# rc2014_I2c_ctrl_clock.net
KiCad netlist of a schematic drawn in EAGLE
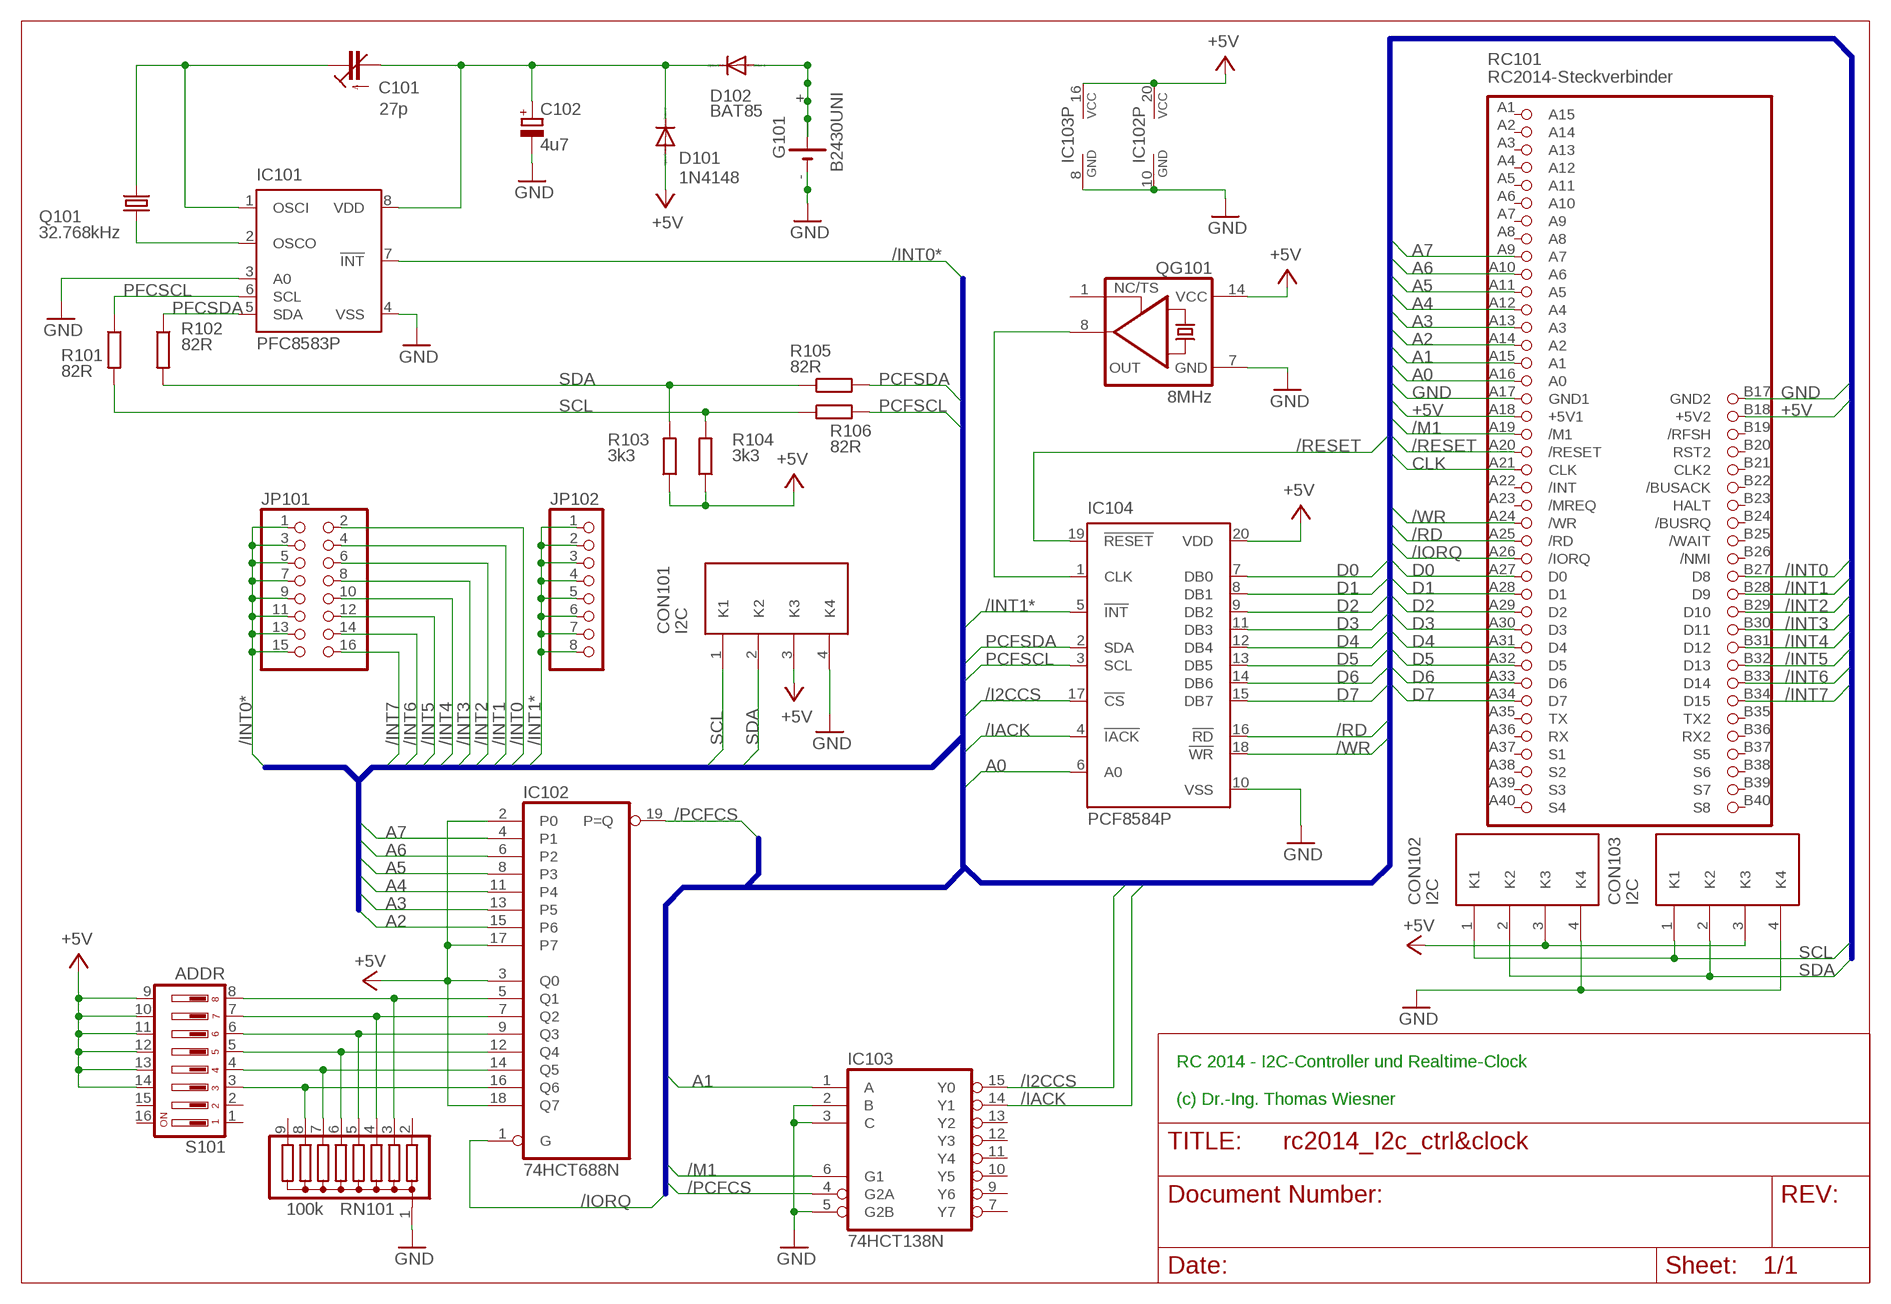
[diagram p0: schematic, sheet 1]

(export (version "E")
  (design (tool "Eeschema 10.0.6"))
  (components
    (comp (ref "C101")
      (value "27p")
      (footprint "eagle-import:CTRIM3050.504")
      (libsource (lib "eagle-import") (part "C-TRIMM3050.504"))
    )
    (comp (ref "C102")
      (value "4u7")
      (footprint "eagle-import:E2,5-6")
      (libsource (lib "eagle-import") (part "CPOL-EUE2.5-6"))
    )
    (comp (ref "CON101")
      (value "I2C")
      (footprint "eagle-import:JST-04-ST90")
      (libsource (lib "eagle-import") (part "SEEED-GROVE"))
    )
    (comp (ref "CON102")
      (value "I2C")
      (footprint "eagle-import:JST-04-ST90")
      (libsource (lib "eagle-import") (part "SEEED-GROVE"))
    )
    (comp (ref "CON103")
      (value "I2C")
      (footprint "eagle-import:JST-04-ST90")
      (libsource (lib "eagle-import") (part "SEEED-GROVE"))
    )
    (comp (ref "D101")
      (value "1N4148")
      (footprint "eagle-import:DO35-7")
      (libsource (lib "eagle-import") (part "1N4148DO35-7"))
    )
    (comp (ref "D102")
      (value "BAT85")
      (footprint "eagle-import:DO34-7")
      (libsource (lib "eagle-import") (part "BAT81"))
    )
    (comp (ref "G101")
      (value "B2430UNI")
      (footprint "eagle-import:B2430UNI")
      (libsource (lib "eagle-import") (part "B2430UNI"))
    )
    (comp (ref "IC101")
      (value "PFC8583P")
      (footprint "eagle-import:DIL08")
      (libsource (lib "eagle-import") (part "PFC8583P"))
    )
    (comp (ref "IC102")
      (value "74HCT688N")
      (footprint "eagle-import:DIL20")
      (libsource (lib "eagle-import") (part "74688NHCT"))
    )
    (comp (ref "IC103")
      (value "74HCT138N")
      (footprint "eagle-import:DIL16")
      (libsource (lib "eagle-import") (part "74138NACT"))
    )
    (comp (ref "IC104")
      (value "PCF8584P")
      (footprint "eagle-import:DIL20")
      (fields (field (name "MF") "FARNELL") (field (name "MPN") "PCF8584P,112"))
      (libsource (lib "eagle-import") (part "PCF8584P"))
    )
    (comp (ref "JP101")
      (value "PINHD-2X8")
      (footprint "eagle-import:2X08")
      (libsource (lib "eagle-import") (part "PINHD-2X8"))
    )
    (comp (ref "JP102")
      (value "PINHD-1X8")
      (footprint "eagle-import:1X08")
      (libsource (lib "eagle-import") (part "PINHD-1X8"))
    )
    (comp (ref "Q101")
      (value "32.768kHz")
      (footprint "eagle-import:TC26H")
      (libsource (lib "eagle-import") (part "CRYSTALTC26H"))
    )
    (comp (ref "QG101")
      (value "8MHz")
      (footprint "eagle-import:DIL14S")
      (libsource (lib "eagle-import") (part "XO-14"))
    )
    (comp (ref "R101")
      (value "82R")
      (footprint "eagle-import:0207_10")
      (libsource (lib "eagle-import") (part "R-EU_0207/10"))
    )
    (comp (ref "R102")
      (value "82R")
      (footprint "eagle-import:0207_10")
      (libsource (lib "eagle-import") (part "R-EU_0207/10"))
    )
    (comp (ref "R103")
      (value "3k3")
      (footprint "eagle-import:0207_10")
      (libsource (lib "eagle-import") (part "R-EU_0207/10"))
    )
    (comp (ref "R104")
      (value "3k3")
      (footprint "eagle-import:0207_10")
      (libsource (lib "eagle-import") (part "R-EU_0207/10"))
    )
    (comp (ref "R105")
      (value "82R")
      (footprint "eagle-import:0207_10")
      (libsource (lib "eagle-import") (part "R-EU_0207/10"))
    )
    (comp (ref "R106")
      (value "82R")
      (footprint "eagle-import:0207_10")
      (libsource (lib "eagle-import") (part "R-EU_0207/10"))
    )
    (comp (ref "RC101")
      (value "RC2014-Steckverbinder")
      (footprint "eagle-import:RC2014-STECKER")
      (libsource (lib "eagle-import") (part "RC2014STECKER"))
    )
    (comp (ref "RN101")
      (value "100k")
      (footprint "eagle-import:SIL9")
      (libsource (lib "eagle-import") (part "G08R"))
    )
    (comp (ref "S101")
      (value "ADDR")
      (footprint "eagle-import:DS-08")
      (fields (field (name "MPN") "DS08"))
      (libsource (lib "eagle-import") (part "DS08"))
    )
  )
  (nets
    (net (code "1") (name "+5V") (class "Default")
      (node (ref "CON101") (pin "3") (pinfunction "K3_3") (pintype "bidirectional"))
      (node (ref "CON102") (pin "3") (pinfunction "K3_3") (pintype "bidirectional"))
      (node (ref "CON103") (pin "3") (pinfunction "K3_3") (pintype "bidirectional"))
      (node (ref "D101") (pin "A") (pinfunction "A_A") (pintype "passive"))
      (node (ref "IC102") (pin "17") (pinfunction "P7_17") (pintype "input"))
      (node (ref "IC102") (pin "18") (pinfunction "Q7_18") (pintype "input"))
      (node (ref "IC102") (pin "2") (pinfunction "P0_2") (pintype "input"))
      (node (ref "IC102") (pin "20") (pinfunction "VCC_20") (pintype "power_in"))
      (node (ref "IC102") (pin "3") (pinfunction "Q0_3") (pintype "input"))
      (node (ref "IC103") (pin "16") (pinfunction "VCC_16") (pintype "power_in"))
      (node (ref "IC104") (pin "20") (pinfunction "VDD_20") (pintype "power_in"))
      (node (ref "QG101") (pin "14") (pinfunction "VCC_14") (pintype "power_in"))
      (node (ref "R103") (pin "1") (pinfunction "1_1") (pintype "passive"))
      (node (ref "R104") (pin "1") (pinfunction "1_1") (pintype "passive"))
      (node (ref "RC101") (pin "A18") (pinfunction "+5V1_A18") (pintype "passive"))
      (node (ref "RC101") (pin "B18") (pinfunction "+5V2_B18") (pintype "passive"))
      (node (ref "S101") (pin "10") (pinfunction "10_10") (pintype "passive"))
      (node (ref "S101") (pin "11") (pinfunction "11_11") (pintype "passive"))
      (node (ref "S101") (pin "12") (pinfunction "12_12") (pintype "passive"))
      (node (ref "S101") (pin "13") (pinfunction "13_13") (pintype "passive"))
      (node (ref "S101") (pin "14") (pinfunction "14_14") (pintype "passive"))
      (node (ref "S101") (pin "9") (pinfunction "9_9") (pintype "passive"))
    )
    (net (code "2") (name "/A0") (class "Default")
      (node (ref "IC104") (pin "6") (pinfunction "A0_6") (pintype "input"))
      (node (ref "RC101") (pin "A16") (pinfunction "A0_A16") (pintype "passive"))
    )
    (net (code "3") (name "/A1") (class "Default")
      (node (ref "IC103") (pin "1") (pinfunction "A_1") (pintype "input"))
      (node (ref "RC101") (pin "A15") (pinfunction "A1_A15") (pintype "passive"))
    )
    (net (code "4") (name "/A2") (class "Default")
      (node (ref "IC102") (pin "15") (pinfunction "P6_15") (pintype "input"))
      (node (ref "RC101") (pin "A14") (pinfunction "A2_A14") (pintype "passive"))
    )
    (net (code "5") (name "/A3") (class "Default")
      (node (ref "IC102") (pin "13") (pinfunction "P5_13") (pintype "input"))
      (node (ref "RC101") (pin "A13") (pinfunction "A3_A13") (pintype "passive"))
    )
    (net (code "6") (name "/A4") (class "Default")
      (node (ref "IC102") (pin "11") (pinfunction "P4_11") (pintype "input"))
      (node (ref "RC101") (pin "A12") (pinfunction "A4_A12") (pintype "passive"))
    )
    (net (code "7") (name "/A5") (class "Default")
      (node (ref "IC102") (pin "8") (pinfunction "P3_8") (pintype "input"))
      (node (ref "RC101") (pin "A11") (pinfunction "A5_A11") (pintype "passive"))
    )
    (net (code "8") (name "/A6") (class "Default")
      (node (ref "IC102") (pin "6") (pinfunction "P2_6") (pintype "input"))
      (node (ref "RC101") (pin "A10") (pinfunction "A6_A10") (pintype "passive"))
    )
    (net (code "9") (name "/A7") (class "Default")
      (node (ref "IC102") (pin "4") (pinfunction "P1_4") (pintype "input"))
      (node (ref "RC101") (pin "A9") (pinfunction "A7_A9") (pintype "passive"))
    )
    (net (code "10") (name "/CLK") (class "Default")
      (node (ref "RC101") (pin "A21") (pinfunction "CLK_A21") (pintype "passive"))
    )
    (net (code "11") (name "/D0") (class "Default")
      (node (ref "IC104") (pin "7") (pinfunction "DB0_7") (pintype "bidirectional"))
      (node (ref "RC101") (pin "A27") (pinfunction "D0_A27") (pintype "passive"))
    )
    (net (code "12") (name "/D1") (class "Default")
      (node (ref "IC104") (pin "8") (pinfunction "DB1_8") (pintype "bidirectional"))
      (node (ref "RC101") (pin "A28") (pinfunction "D1_A28") (pintype "passive"))
    )
    (net (code "13") (name "/D2") (class "Default")
      (node (ref "IC104") (pin "9") (pinfunction "DB2_9") (pintype "bidirectional"))
      (node (ref "RC101") (pin "A29") (pinfunction "D2_A29") (pintype "passive"))
    )
    (net (code "14") (name "/D3") (class "Default")
      (node (ref "IC104") (pin "11") (pinfunction "DB3_11") (pintype "bidirectional"))
      (node (ref "RC101") (pin "A30") (pinfunction "D3_A30") (pintype "passive"))
    )
    (net (code "15") (name "/D4") (class "Default")
      (node (ref "IC104") (pin "12") (pinfunction "DB4_12") (pintype "bidirectional"))
      (node (ref "RC101") (pin "A31") (pinfunction "D4_A31") (pintype "passive"))
    )
    (net (code "16") (name "/D5") (class "Default")
      (node (ref "IC104") (pin "13") (pinfunction "DB5_13") (pintype "bidirectional"))
      (node (ref "RC101") (pin "A32") (pinfunction "D5_A32") (pintype "passive"))
    )
    (net (code "17") (name "/D6") (class "Default")
      (node (ref "IC104") (pin "14") (pinfunction "DB6_14") (pintype "bidirectional"))
      (node (ref "RC101") (pin "A33") (pinfunction "D6_A33") (pintype "passive"))
    )
    (net (code "18") (name "/D7") (class "Default")
      (node (ref "IC104") (pin "15") (pinfunction "DB7_15") (pintype "bidirectional"))
      (node (ref "RC101") (pin "A34") (pinfunction "D7_A34") (pintype "passive"))
    )
    (net (code "19") (name "/PCFSCL") (class "Default")
      (node (ref "IC104") (pin "3") (pinfunction "SCL_3") (pintype "input"))
      (node (ref "R106") (pin "2") (pinfunction "2_2") (pintype "passive"))
    )
    (net (code "20") (name "/PCFSDA") (class "Default")
      (node (ref "IC104") (pin "2") (pinfunction "SDA_2") (pintype "bidirectional"))
      (node (ref "R105") (pin "2") (pinfunction "2_2") (pintype "passive"))
    )
    (net (code "21") (name "/PFCSCL") (class "Default")
      (node (ref "IC101") (pin "6") (pinfunction "SCL_6") (pintype "input"))
      (node (ref "R101") (pin "1") (pinfunction "1_1") (pintype "passive"))
    )
    (net (code "22") (name "/PFCSDA") (class "Default")
      (node (ref "IC101") (pin "5") (pinfunction "SDA_5") (pintype "bidirectional"))
      (node (ref "R102") (pin "1") (pinfunction "1_1") (pintype "passive"))
    )
    (net (code "23") (name "/SCL") (class "Default")
      (node (ref "CON101") (pin "1") (pinfunction "K1_1") (pintype "bidirectional"))
      (node (ref "CON102") (pin "1") (pinfunction "K1_1") (pintype "bidirectional"))
      (node (ref "CON103") (pin "1") (pinfunction "K1_1") (pintype "bidirectional"))
      (node (ref "R101") (pin "2") (pinfunction "2_2") (pintype "passive"))
      (node (ref "R104") (pin "2") (pinfunction "2_2") (pintype "passive"))
      (node (ref "R106") (pin "1") (pinfunction "1_1") (pintype "passive"))
    )
    (net (code "24") (name "/SDA") (class "Default")
      (node (ref "CON101") (pin "2") (pinfunction "K2_2") (pintype "bidirectional"))
      (node (ref "CON102") (pin "2") (pinfunction "K2_2") (pintype "bidirectional"))
      (node (ref "CON103") (pin "2") (pinfunction "K2_2") (pintype "bidirectional"))
      (node (ref "R102") (pin "2") (pinfunction "2_2") (pintype "passive"))
      (node (ref "R103") (pin "2") (pinfunction "2_2") (pintype "passive"))
      (node (ref "R105") (pin "1") (pinfunction "1_1") (pintype "passive"))
    )
    (net (code "25") (name "/{slash}I2CCS") (class "Default")
      (node (ref "IC103") (pin "15") (pinfunction "Y0_15") (pintype "output"))
      (node (ref "IC104") (pin "17") (pinfunction "~{CS}_17") (pintype "input"))
    )
    (net (code "26") (name "/{slash}IACK") (class "Default")
      (node (ref "IC103") (pin "14") (pinfunction "Y1_14") (pintype "output"))
      (node (ref "IC104") (pin "4") (pinfunction "~{IACK}_4") (pintype "input"))
    )
    (net (code "27") (name "/{slash}INT0") (class "Default")
      (node (ref "JP101") (pin "2") (pinfunction "2_2") (pintype "passive"))
      (node (ref "RC101") (pin "B27") (pinfunction "D8_B27") (pintype "passive"))
    )
    (net (code "28") (name "/{slash}INT0*") (class "Default")
      (node (ref "IC101") (pin "7") (pinfunction "~{INT}_7") (pintype "output"))
      (node (ref "JP101") (pin "1") (pinfunction "1_1") (pintype "passive"))
      (node (ref "JP101") (pin "11") (pinfunction "11_11") (pintype "passive"))
      (node (ref "JP101") (pin "13") (pinfunction "13_13") (pintype "passive"))
      (node (ref "JP101") (pin "15") (pinfunction "15_15") (pintype "passive"))
      (node (ref "JP101") (pin "3") (pinfunction "3_3") (pintype "passive"))
      (node (ref "JP101") (pin "5") (pinfunction "5_5") (pintype "passive"))
      (node (ref "JP101") (pin "7") (pinfunction "7_7") (pintype "passive"))
      (node (ref "JP101") (pin "9") (pinfunction "9_9") (pintype "passive"))
    )
    (net (code "29") (name "/{slash}INT1") (class "Default")
      (node (ref "JP101") (pin "4") (pinfunction "4_4") (pintype "passive"))
      (node (ref "RC101") (pin "B28") (pinfunction "D9_B28") (pintype "passive"))
    )
    (net (code "30") (name "/{slash}INT1*") (class "Default")
      (node (ref "IC104") (pin "5") (pinfunction "~{INT}_5") (pintype "output"))
      (node (ref "JP102") (pin "1") (pinfunction "1_1") (pintype "passive"))
      (node (ref "JP102") (pin "2") (pinfunction "2_2") (pintype "passive"))
      (node (ref "JP102") (pin "3") (pinfunction "3_3") (pintype "passive"))
      (node (ref "JP102") (pin "4") (pinfunction "4_4") (pintype "passive"))
      (node (ref "JP102") (pin "5") (pinfunction "5_5") (pintype "passive"))
      (node (ref "JP102") (pin "6") (pinfunction "6_6") (pintype "passive"))
      (node (ref "JP102") (pin "7") (pinfunction "7_7") (pintype "passive"))
      (node (ref "JP102") (pin "8") (pinfunction "8_8") (pintype "passive"))
    )
    (net (code "31") (name "/{slash}INT2") (class "Default")
      (node (ref "JP101") (pin "6") (pinfunction "6_6") (pintype "passive"))
      (node (ref "RC101") (pin "B29") (pinfunction "D10_B29") (pintype "passive"))
    )
    (net (code "32") (name "/{slash}INT3") (class "Default")
      (node (ref "JP101") (pin "8") (pinfunction "8_8") (pintype "passive"))
      (node (ref "RC101") (pin "B30") (pinfunction "D11_B30") (pintype "passive"))
    )
    (net (code "33") (name "/{slash}INT4") (class "Default")
      (node (ref "JP101") (pin "10") (pinfunction "10_10") (pintype "passive"))
      (node (ref "RC101") (pin "B31") (pinfunction "D12_B31") (pintype "passive"))
    )
    (net (code "34") (name "/{slash}INT5") (class "Default")
      (node (ref "JP101") (pin "12") (pinfunction "12_12") (pintype "passive"))
      (node (ref "RC101") (pin "B32") (pinfunction "D13_B32") (pintype "passive"))
    )
    (net (code "35") (name "/{slash}INT6") (class "Default")
      (node (ref "JP101") (pin "14") (pinfunction "14_14") (pintype "passive"))
      (node (ref "RC101") (pin "B33") (pinfunction "D14_B33") (pintype "passive"))
    )
    (net (code "36") (name "/{slash}INT7") (class "Default")
      (node (ref "JP101") (pin "16") (pinfunction "16_16") (pintype "passive"))
      (node (ref "RC101") (pin "B34") (pinfunction "D15_B34") (pintype "passive"))
    )
    (net (code "37") (name "/{slash}IORQ") (class "Default")
      (node (ref "IC102") (pin "1") (pinfunction "G_1") (pintype "input"))
      (node (ref "RC101") (pin "A26") (pinfunction "/IORQ_A26") (pintype "passive"))
    )
    (net (code "38") (name "/{slash}M1") (class "Default")
      (node (ref "IC103") (pin "6") (pinfunction "G1_6") (pintype "input"))
      (node (ref "RC101") (pin "A19") (pinfunction "/M1_A19") (pintype "passive"))
    )
    (net (code "39") (name "/{slash}PCFCS") (class "Default")
      (node (ref "IC102") (pin "19") (pinfunction "P=Q_19") (pintype "output"))
      (node (ref "IC103") (pin "4") (pinfunction "G2A_4") (pintype "input"))
    )
    (net (code "40") (name "/{slash}RD") (class "Default")
      (node (ref "IC104") (pin "16") (pinfunction "~{RD}_16") (pintype "input"))
      (node (ref "RC101") (pin "A25") (pinfunction "/RD_A25") (pintype "passive"))
    )
    (net (code "41") (name "/{slash}RESET") (class "Default")
      (node (ref "IC104") (pin "19") (pinfunction "~{RESET}_19") (pintype "input"))
      (node (ref "RC101") (pin "A20") (pinfunction "/RESET_A20") (pintype "passive"))
    )
    (net (code "42") (name "/{slash}WR") (class "Default")
      (node (ref "IC104") (pin "18") (pinfunction "~{WR}_18") (pintype "input"))
      (node (ref "RC101") (pin "A24") (pinfunction "/WR_A24") (pintype "passive"))
    )
    (net (code "43") (name "GND") (class "Default")
      (node (ref "C102") (pin "-") (pinfunction "-_-") (pintype "passive"))
      (node (ref "CON101") (pin "4") (pinfunction "K4_4") (pintype "bidirectional"))
      (node (ref "CON102") (pin "4") (pinfunction "K4_4") (pintype "bidirectional"))
      (node (ref "CON103") (pin "4") (pinfunction "K4_4") (pintype "bidirectional"))
      (node (ref "G101") (pin "-") (pinfunction "-_-") (pintype "passive"))
      (node (ref "G101") (pin "-@1") (pinfunction "-_-@1") (pintype "passive"))
      (node (ref "IC101") (pin "3") (pinfunction "A0_3") (pintype "input"))
      (node (ref "IC101") (pin "4") (pinfunction "VSS_4") (pintype "power_in"))
      (node (ref "IC102") (pin "10") (pinfunction "GND_10") (pintype "power_in"))
      (node (ref "IC103") (pin "2") (pinfunction "B_2") (pintype "input"))
      (node (ref "IC103") (pin "3") (pinfunction "C_3") (pintype "input"))
      (node (ref "IC103") (pin "5") (pinfunction "G2B_5") (pintype "input"))
      (node (ref "IC103") (pin "8") (pinfunction "GND_8") (pintype "power_in"))
      (node (ref "IC104") (pin "10") (pinfunction "VSS_10") (pintype "power_in"))
      (node (ref "QG101") (pin "7") (pinfunction "GND_7") (pintype "power_in"))
      (node (ref "RC101") (pin "A17") (pinfunction "GND1_A17") (pintype "passive"))
      (node (ref "RC101") (pin "B17") (pinfunction "GND2_B17") (pintype "passive"))
      (node (ref "RN101") (pin "1") (pinfunction "1_1") (pintype "passive"))
    )
    (net (code "44") (name "Net-(C101-A)") (class "Default")
      (node (ref "C101") (pin "2") (pinfunction "A_2") (pintype "passive"))
      (node (ref "C102") (pin "+") (pinfunction "+_+") (pintype "passive"))
      (node (ref "D101") (pin "C") (pinfunction "C_C") (pintype "passive"))
      (node (ref "D102") (pin "C") (pinfunction "C_C") (pintype "passive"))
      (node (ref "IC101") (pin "8") (pinfunction "VDD_8") (pintype "power_in"))
    )
    (net (code "45") (name "Net-(C101-E)") (class "Default")
      (node (ref "C101") (pin "1") (pinfunction "E_1") (pintype "passive"))
      (node (ref "IC101") (pin "1") (pinfunction "OSCI_1") (pintype "input"))
      (node (ref "Q101") (pin "2") (pinfunction "2_2") (pintype "passive"))
    )
    (net (code "46") (name "Net-(D102-PadA)") (class "Default")
      (node (ref "D102") (pin "A") (pinfunction "A_A") (pintype "passive"))
      (node (ref "G101") (pin "+") (pinfunction "+_+") (pintype "passive"))
      (node (ref "G101") (pin "+@1") (pinfunction "+_+@1") (pintype "passive"))
      (node (ref "G101") (pin "+@2") (pinfunction "+_+@2") (pintype "passive"))
      (node (ref "G101") (pin "+@3") (pinfunction "+_+@3") (pintype "passive"))
      (node (ref "G101") (pin "+@4") (pinfunction "+_+@4") (pintype "passive"))
    )
    (net (code "47") (name "Net-(IC101-OSCO)") (class "Default")
      (node (ref "IC101") (pin "2") (pinfunction "OSCO_2") (pintype "output"))
      (node (ref "Q101") (pin "1") (pinfunction "1_1") (pintype "passive"))
    )
    (net (code "48") (name "Net-(IC102A-Q1)") (class "Default")
      (node (ref "IC102") (pin "5") (pinfunction "Q1_5") (pintype "input"))
      (node (ref "RN101") (pin "3") (pinfunction "3_3") (pintype "passive"))
      (node (ref "S101") (pin "8") (pinfunction "8_8") (pintype "passive"))
    )
    (net (code "49") (name "Net-(IC102A-Q2)") (class "Default")
      (node (ref "IC102") (pin "7") (pinfunction "Q2_7") (pintype "input"))
      (node (ref "RN101") (pin "4") (pinfunction "4_4") (pintype "passive"))
      (node (ref "S101") (pin "7") (pinfunction "7_7") (pintype "passive"))
    )
    (net (code "50") (name "Net-(IC102A-Q3)") (class "Default")
      (node (ref "IC102") (pin "9") (pinfunction "Q3_9") (pintype "input"))
      (node (ref "RN101") (pin "5") (pinfunction "5_5") (pintype "passive"))
      (node (ref "S101") (pin "6") (pinfunction "6_6") (pintype "passive"))
    )
    (net (code "51") (name "Net-(IC102A-Q4)") (class "Default")
      (node (ref "IC102") (pin "12") (pinfunction "Q4_12") (pintype "input"))
      (node (ref "RN101") (pin "6") (pinfunction "6_6") (pintype "passive"))
      (node (ref "S101") (pin "5") (pinfunction "5_5") (pintype "passive"))
    )
    (net (code "52") (name "Net-(IC102A-Q5)") (class "Default")
      (node (ref "IC102") (pin "14") (pinfunction "Q5_14") (pintype "input"))
      (node (ref "RN101") (pin "7") (pinfunction "7_7") (pintype "passive"))
      (node (ref "S101") (pin "4") (pinfunction "4_4") (pintype "passive"))
    )
    (net (code "53") (name "Net-(IC102A-Q6)") (class "Default")
      (node (ref "IC102") (pin "16") (pinfunction "Q6_16") (pintype "input"))
      (node (ref "RN101") (pin "8") (pinfunction "8_8") (pintype "passive"))
      (node (ref "S101") (pin "3") (pinfunction "3_3") (pintype "passive"))
    )
    (net (code "54") (name "Net-(IC104-CLK)") (class "Default")
      (node (ref "IC104") (pin "1") (pinfunction "CLK_1") (pintype "input"))
      (node (ref "QG101") (pin "8") (pinfunction "OUT_8") (pintype "output"))
    )
    (net (code "55") (name "unconnected-(IC103A-Y2-Pad13)") (class "Default")
      (node (ref "IC103") (pin "13") (pinfunction "Y2_13") (pintype "output"))
    )
    (net (code "56") (name "unconnected-(IC103A-Y3-Pad12)") (class "Default")
      (node (ref "IC103") (pin "12") (pinfunction "Y3_12") (pintype "output"))
    )
    (net (code "57") (name "unconnected-(IC103A-Y4-Pad11)") (class "Default")
      (node (ref "IC103") (pin "11") (pinfunction "Y4_11") (pintype "output"))
    )
    (net (code "58") (name "unconnected-(IC103A-Y5-Pad10)") (class "Default")
      (node (ref "IC103") (pin "10") (pinfunction "Y5_10") (pintype "output"))
    )
    (net (code "59") (name "unconnected-(IC103A-Y6-Pad9)") (class "Default")
      (node (ref "IC103") (pin "9") (pinfunction "Y6_9") (pintype "output"))
    )
    (net (code "60") (name "unconnected-(IC103A-Y7-Pad7)") (class "Default")
      (node (ref "IC103") (pin "7") (pinfunction "Y7_7") (pintype "output"))
    )
    (net (code "61") (name "unconnected-(QG101-TS-Pad1)") (class "Default")
      (node (ref "QG101") (pin "1") (pinfunction "TS_1") (pintype "passive"))
    )
    (net (code "62") (name "unconnected-(RC101-A9-PadA7)") (class "Default")
      (node (ref "RC101") (pin "A7") (pinfunction "A9_A7") (pintype "passive"))
    )
    (net (code "63") (name "unconnected-(RC101-A10-PadA6)") (class "Default")
      (node (ref "RC101") (pin "A6") (pinfunction "A10_A6") (pintype "passive"))
    )
    (net (code "64") (name "unconnected-(RC101-A11-PadA5)") (class "Default")
      (node (ref "RC101") (pin "A5") (pinfunction "A11_A5") (pintype "passive"))
    )
    (net (code "65") (name "unconnected-(RC101-A12-PadA4)") (class "Default")
      (node (ref "RC101") (pin "A4") (pinfunction "A12_A4") (pintype "passive"))
    )
    (net (code "66") (name "unconnected-(RC101-A13-PadA3)") (class "Default")
      (node (ref "RC101") (pin "A3") (pinfunction "A13_A3") (pintype "passive"))
    )
    (net (code "67") (name "unconnected-(RC101-A14-PadA2)") (class "Default")
      (node (ref "RC101") (pin "A2") (pinfunction "A14_A2") (pintype "passive"))
    )
    (net (code "68") (name "unconnected-(RC101-A15-PadA1)") (class "Default")
      (node (ref "RC101") (pin "A1") (pinfunction "A15_A1") (pintype "passive"))
    )
    (net (code "69") (name "unconnected-(RC101-CLK2-PadB21)") (class "Default")
      (node (ref "RC101") (pin "B21") (pinfunction "CLK2_B21") (pintype "passive"))
    )
    (net (code "70") (name "unconnected-(RC101-HALT-PadB23)") (class "Default")
      (node (ref "RC101") (pin "B23") (pinfunction "HALT_B23") (pintype "passive"))
    )
    (net (code "71") (name "unconnected-(RC101-PadA8)") (class "Default")
      (node (ref "RC101") (pin "A8") (pinfunction "A8_A8") (pintype "passive"))
    )
    (net (code "72") (name "unconnected-(RC101-RST2-PadB20)") (class "Default")
      (node (ref "RC101") (pin "B20") (pinfunction "RST2_B20") (pintype "passive"))
    )
    (net (code "73") (name "unconnected-(RC101-RX-PadA36)") (class "Default")
      (node (ref "RC101") (pin "A36") (pinfunction "RX_A36") (pintype "passive"))
    )
    (net (code "74") (name "unconnected-(RC101-RX2-PadB36)") (class "Default")
      (node (ref "RC101") (pin "B36") (pinfunction "RX2_B36") (pintype "passive"))
    )
    (net (code "75") (name "unconnected-(RC101-S1-PadA37)") (class "Default")
      (node (ref "RC101") (pin "A37") (pinfunction "S1_A37") (pintype "passive"))
    )
    (net (code "76") (name "unconnected-(RC101-S2-PadA38)") (class "Default")
      (node (ref "RC101") (pin "A38") (pinfunction "S2_A38") (pintype "passive"))
    )
    (net (code "77") (name "unconnected-(RC101-S3-PadA39)") (class "Default")
      (node (ref "RC101") (pin "A39") (pinfunction "S3_A39") (pintype "passive"))
    )
    (net (code "78") (name "unconnected-(RC101-S4-PadA40)") (class "Default")
      (node (ref "RC101") (pin "A40") (pinfunction "S4_A40") (pintype "passive"))
    )
    (net (code "79") (name "unconnected-(RC101-S5-PadB37)") (class "Default")
      (node (ref "RC101") (pin "B37") (pinfunction "S5_B37") (pintype "passive"))
    )
    (net (code "80") (name "unconnected-(RC101-S6-PadB38)") (class "Default")
      (node (ref "RC101") (pin "B38") (pinfunction "S6_B38") (pintype "passive"))
    )
    (net (code "81") (name "unconnected-(RC101-S7-PadB39)") (class "Default")
      (node (ref "RC101") (pin "B39") (pinfunction "S7_B39") (pintype "passive"))
    )
    (net (code "82") (name "unconnected-(RC101-S8-PadB40)") (class "Default")
      (node (ref "RC101") (pin "B40") (pinfunction "S8_B40") (pintype "passive"))
    )
    (net (code "83") (name "unconnected-(RC101-TX-PadA35)") (class "Default")
      (node (ref "RC101") (pin "A35") (pinfunction "TX_A35") (pintype "passive"))
    )
    (net (code "84") (name "unconnected-(RC101-TX2-PadB35)") (class "Default")
      (node (ref "RC101") (pin "B35") (pinfunction "TX2_B35") (pintype "passive"))
    )
    (net (code "85") (name "unconnected-(RC101-{slash}BUSACK-PadB22)") (class "Default")
      (node (ref "RC101") (pin "B22") (pinfunction "/BUSACK_B22") (pintype "passive"))
    )
    (net (code "86") (name "unconnected-(RC101-{slash}BUSRQ-PadB24)") (class "Default")
      (node (ref "RC101") (pin "B24") (pinfunction "/BUSRQ_B24") (pintype "passive"))
    )
    (net (code "87") (name "unconnected-(RC101-{slash}INT-PadA22)") (class "Default")
      (node (ref "RC101") (pin "A22") (pinfunction "/INT_A22") (pintype "passive"))
    )
    (net (code "88") (name "unconnected-(RC101-{slash}MREQ-PadA23)") (class "Default")
      (node (ref "RC101") (pin "A23") (pinfunction "/MREQ_A23") (pintype "passive"))
    )
    (net (code "89") (name "unconnected-(RC101-{slash}NMI-PadB26)") (class "Default")
      (node (ref "RC101") (pin "B26") (pinfunction "/NMI_B26") (pintype "passive"))
    )
    (net (code "90") (name "unconnected-(RC101-{slash}RFSH-PadB19)") (class "Default")
      (node (ref "RC101") (pin "B19") (pinfunction "/RFSH_B19") (pintype "passive"))
    )
    (net (code "91") (name "unconnected-(RC101-{slash}WAIT-PadB25)") (class "Default")
      (node (ref "RC101") (pin "B25") (pinfunction "/WAIT_B25") (pintype "passive"))
    )
    (net (code "92") (name "unconnected-(RN101-Pad2)") (class "Default")
      (node (ref "RN101") (pin "2") (pinfunction "2_2") (pintype "passive"))
    )
    (net (code "93") (name "unconnected-(RN101-Pad9)") (class "Default")
      (node (ref "RN101") (pin "9") (pinfunction "9_9") (pintype "passive"))
    )
    (net (code "94") (name "unconnected-(S101-Pad1)") (class "Default")
      (node (ref "S101") (pin "1") (pinfunction "1_1") (pintype "passive"))
    )
    (net (code "95") (name "unconnected-(S101-Pad2)") (class "Default")
      (node (ref "S101") (pin "2") (pinfunction "2_2") (pintype "passive"))
    )
    (net (code "96") (name "unconnected-(S101-Pad15)") (class "Default")
      (node (ref "S101") (pin "15") (pinfunction "15_15") (pintype "passive"))
    )
    (net (code "97") (name "unconnected-(S101-Pad16)") (class "Default")
      (node (ref "S101") (pin "16") (pinfunction "16_16") (pintype "passive"))
    )
  )
)
